# LED_10.net
KiCad netlist of a schematic drawn in EAGLE
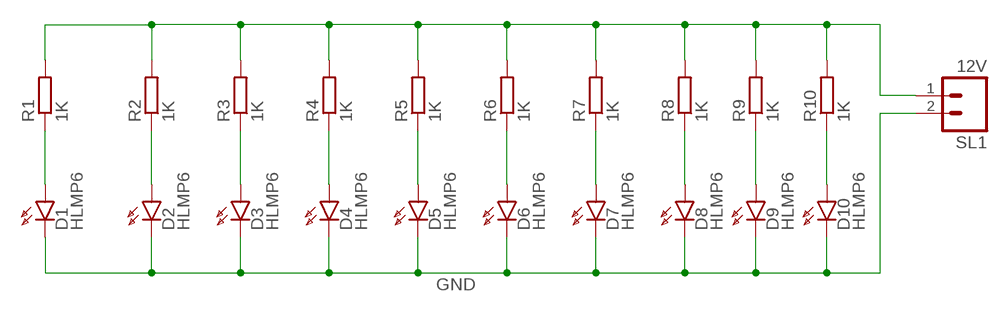
[diagram p0: schematic, sheet 1]

(export (version "E")
  (design (tool "Eeschema 10.0.6"))
  (components
    (comp (ref "D1")
      (value "HLMP6")
      (footprint "eagle-import:HLMP6")
      (fields (field (name "MF") "AGILENT TECHNOLOGIES") (field (name "MPN") "HLMP-6500"))
      (libsource (lib "eagle-import") (part "HLMP6"))
    )
    (comp (ref "D2")
      (value "HLMP6")
      (footprint "eagle-import:HLMP6")
      (fields (field (name "MF") "AGILENT TECHNOLOGIES") (field (name "MPN") "HLMP-6500"))
      (libsource (lib "eagle-import") (part "HLMP6"))
    )
    (comp (ref "D3")
      (value "HLMP6")
      (footprint "eagle-import:HLMP6")
      (fields (field (name "MF") "AGILENT TECHNOLOGIES") (field (name "MPN") "HLMP-6500"))
      (libsource (lib "eagle-import") (part "HLMP6"))
    )
    (comp (ref "D4")
      (value "HLMP6")
      (footprint "eagle-import:HLMP6")
      (fields (field (name "MF") "AGILENT TECHNOLOGIES") (field (name "MPN") "HLMP-6500"))
      (libsource (lib "eagle-import") (part "HLMP6"))
    )
    (comp (ref "D5")
      (value "HLMP6")
      (footprint "eagle-import:HLMP6")
      (fields (field (name "MF") "AGILENT TECHNOLOGIES") (field (name "MPN") "HLMP-6500"))
      (libsource (lib "eagle-import") (part "HLMP6"))
    )
    (comp (ref "D6")
      (value "HLMP6")
      (footprint "eagle-import:HLMP6")
      (fields (field (name "MF") "AGILENT TECHNOLOGIES") (field (name "MPN") "HLMP-6500"))
      (libsource (lib "eagle-import") (part "HLMP6"))
    )
    (comp (ref "D7")
      (value "HLMP6")
      (footprint "eagle-import:HLMP6")
      (fields (field (name "MF") "AGILENT TECHNOLOGIES") (field (name "MPN") "HLMP-6500"))
      (libsource (lib "eagle-import") (part "HLMP6"))
    )
    (comp (ref "D8")
      (value "HLMP6")
      (footprint "eagle-import:HLMP6")
      (fields (field (name "MF") "AGILENT TECHNOLOGIES") (field (name "MPN") "HLMP-6500"))
      (libsource (lib "eagle-import") (part "HLMP6"))
    )
    (comp (ref "D9")
      (value "HLMP6")
      (footprint "eagle-import:HLMP6")
      (fields (field (name "MF") "AGILENT TECHNOLOGIES") (field (name "MPN") "HLMP-6500"))
      (libsource (lib "eagle-import") (part "HLMP6"))
    )
    (comp (ref "D10")
      (value "HLMP6")
      (footprint "eagle-import:HLMP6")
      (fields (field (name "MF") "AGILENT TECHNOLOGIES") (field (name "MPN") "HLMP-6500"))
      (libsource (lib "eagle-import") (part "HLMP6"))
    )
    (comp (ref "R1")
      (value "1K")
      (footprint "eagle-import:0204_7")
      (libsource (lib "eagle-import") (part "R-EU_0204/7"))
    )
    (comp (ref "R2")
      (value "1K")
      (footprint "eagle-import:0204_7")
      (libsource (lib "eagle-import") (part "R-EU_0204/7"))
    )
    (comp (ref "R3")
      (value "1K")
      (footprint "eagle-import:0204_7")
      (libsource (lib "eagle-import") (part "R-EU_0204/7"))
    )
    (comp (ref "R4")
      (value "1K")
      (footprint "eagle-import:0204_7")
      (libsource (lib "eagle-import") (part "R-EU_0204/7"))
    )
    (comp (ref "R5")
      (value "1K")
      (footprint "eagle-import:0204_7")
      (libsource (lib "eagle-import") (part "R-EU_0204/7"))
    )
    (comp (ref "R6")
      (value "1K")
      (footprint "eagle-import:0204_7")
      (libsource (lib "eagle-import") (part "R-EU_0204/7"))
    )
    (comp (ref "R7")
      (value "1K")
      (footprint "eagle-import:0204_7")
      (libsource (lib "eagle-import") (part "R-EU_0204/7"))
    )
    (comp (ref "R8")
      (value "1K")
      (footprint "eagle-import:0204_7")
      (libsource (lib "eagle-import") (part "R-EU_0204/7"))
    )
    (comp (ref "R9")
      (value "1K")
      (footprint "eagle-import:0204_7")
      (libsource (lib "eagle-import") (part "R-EU_0204/7"))
    )
    (comp (ref "R10")
      (value "1K")
      (footprint "eagle-import:0204_7")
      (libsource (lib "eagle-import") (part "R-EU_0204/7"))
    )
    (comp (ref "SL1")
      (value "12V")
      (footprint "eagle-import:02P")
      (libsource (lib "eagle-import") (part "M02"))
    )
  )
  (nets
    (net (code "1") (name "/GND") (class "Default")
      (node (ref "D1") (pin "K") (pinfunction "K_K") (pintype "passive"))
      (node (ref "D10") (pin "K") (pinfunction "K_K") (pintype "passive"))
      (node (ref "D2") (pin "K") (pinfunction "K_K") (pintype "passive"))
      (node (ref "D3") (pin "K") (pinfunction "K_K") (pintype "passive"))
      (node (ref "D4") (pin "K") (pinfunction "K_K") (pintype "passive"))
      (node (ref "D5") (pin "K") (pinfunction "K_K") (pintype "passive"))
      (node (ref "D6") (pin "K") (pinfunction "K_K") (pintype "passive"))
      (node (ref "D7") (pin "K") (pinfunction "K_K") (pintype "passive"))
      (node (ref "D8") (pin "K") (pinfunction "K_K") (pintype "passive"))
      (node (ref "D9") (pin "K") (pinfunction "K_K") (pintype "passive"))
      (node (ref "SL1") (pin "2") (pinfunction "2_2") (pintype "passive"))
    )
    (net (code "2") (name "Net-(D1-PadA)") (class "Default")
      (node (ref "D1") (pin "A") (pinfunction "A_A") (pintype "passive"))
      (node (ref "R1") (pin "1") (pinfunction "1_1") (pintype "passive"))
    )
    (net (code "3") (name "Net-(D2-PadA)") (class "Default")
      (node (ref "D2") (pin "A") (pinfunction "A_A") (pintype "passive"))
      (node (ref "R2") (pin "1") (pinfunction "1_1") (pintype "passive"))
    )
    (net (code "4") (name "Net-(D3-PadA)") (class "Default")
      (node (ref "D3") (pin "A") (pinfunction "A_A") (pintype "passive"))
      (node (ref "R3") (pin "1") (pinfunction "1_1") (pintype "passive"))
    )
    (net (code "5") (name "Net-(D4-PadA)") (class "Default")
      (node (ref "D4") (pin "A") (pinfunction "A_A") (pintype "passive"))
      (node (ref "R4") (pin "1") (pinfunction "1_1") (pintype "passive"))
    )
    (net (code "6") (name "Net-(D5-PadA)") (class "Default")
      (node (ref "D5") (pin "A") (pinfunction "A_A") (pintype "passive"))
      (node (ref "R5") (pin "1") (pinfunction "1_1") (pintype "passive"))
    )
    (net (code "7") (name "Net-(D6-PadA)") (class "Default")
      (node (ref "D6") (pin "A") (pinfunction "A_A") (pintype "passive"))
      (node (ref "R6") (pin "1") (pinfunction "1_1") (pintype "passive"))
    )
    (net (code "8") (name "Net-(D7-PadA)") (class "Default")
      (node (ref "D7") (pin "A") (pinfunction "A_A") (pintype "passive"))
      (node (ref "R7") (pin "1") (pinfunction "1_1") (pintype "passive"))
    )
    (net (code "9") (name "Net-(D8-PadA)") (class "Default")
      (node (ref "D8") (pin "A") (pinfunction "A_A") (pintype "passive"))
      (node (ref "R8") (pin "1") (pinfunction "1_1") (pintype "passive"))
    )
    (net (code "10") (name "Net-(D9-PadA)") (class "Default")
      (node (ref "D9") (pin "A") (pinfunction "A_A") (pintype "passive"))
      (node (ref "R9") (pin "1") (pinfunction "1_1") (pintype "passive"))
    )
    (net (code "11") (name "Net-(D10-PadA)") (class "Default")
      (node (ref "D10") (pin "A") (pinfunction "A_A") (pintype "passive"))
      (node (ref "R10") (pin "1") (pinfunction "1_1") (pintype "passive"))
    )
    (net (code "12") (name "Net-(R1-Pad2)") (class "Default")
      (node (ref "R1") (pin "2") (pinfunction "2_2") (pintype "passive"))
      (node (ref "R10") (pin "2") (pinfunction "2_2") (pintype "passive"))
      (node (ref "R2") (pin "2") (pinfunction "2_2") (pintype "passive"))
      (node (ref "R3") (pin "2") (pinfunction "2_2") (pintype "passive"))
      (node (ref "R4") (pin "2") (pinfunction "2_2") (pintype "passive"))
      (node (ref "R5") (pin "2") (pinfunction "2_2") (pintype "passive"))
      (node (ref "R6") (pin "2") (pinfunction "2_2") (pintype "passive"))
      (node (ref "R7") (pin "2") (pinfunction "2_2") (pintype "passive"))
      (node (ref "R8") (pin "2") (pinfunction "2_2") (pintype "passive"))
      (node (ref "R9") (pin "2") (pinfunction "2_2") (pintype "passive"))
      (node (ref "SL1") (pin "1") (pinfunction "1_1") (pintype "passive"))
    )
  )
)
